# AJH_100m_ADSR_1_01.net
KiCad netlist of a schematic drawn in EAGLE
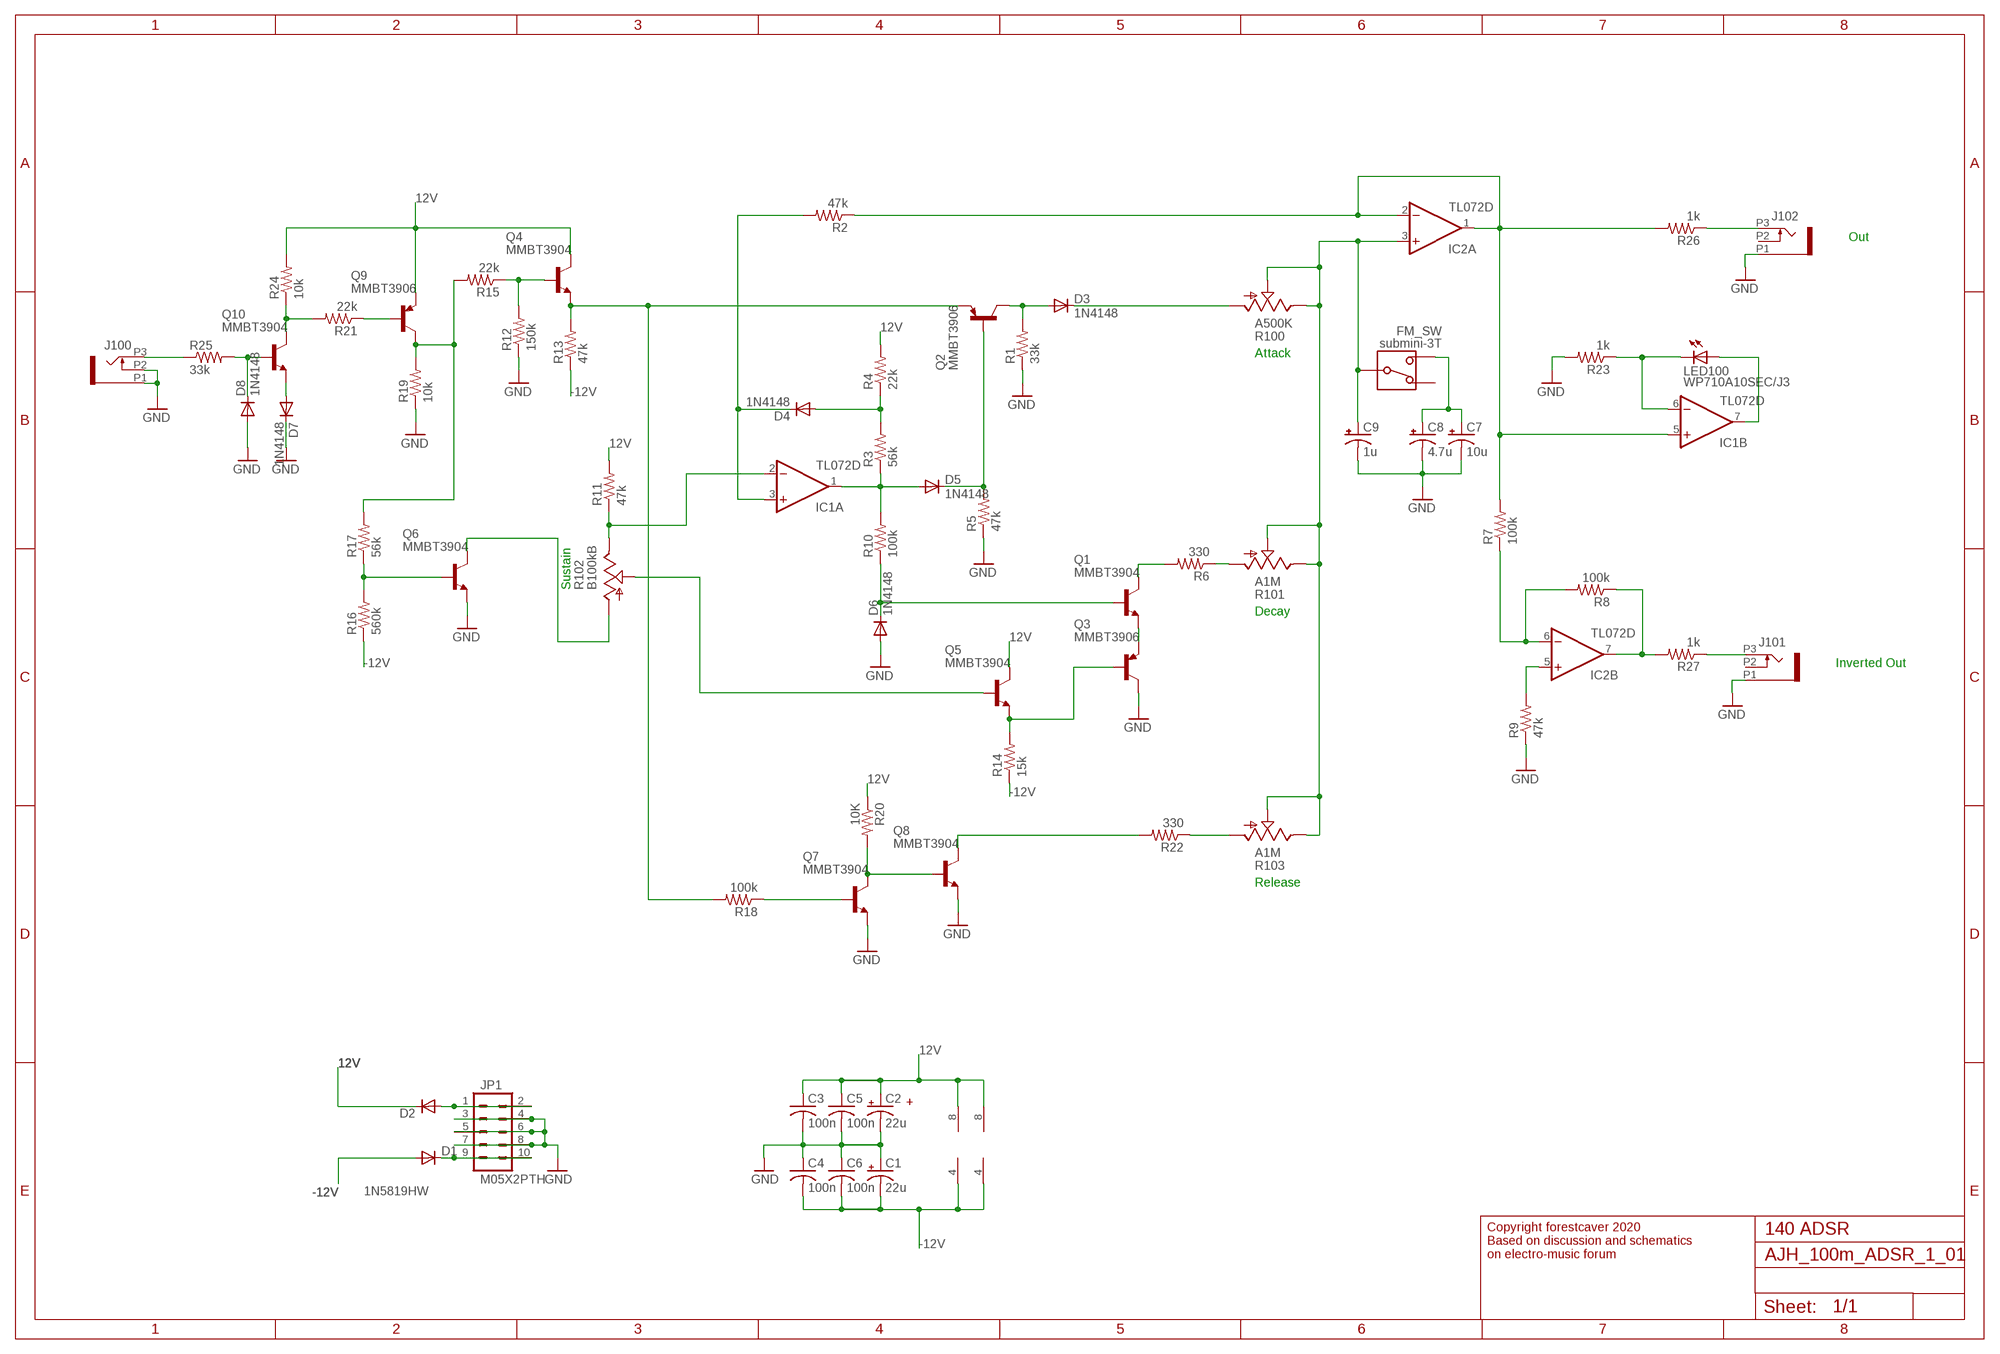
[diagram p0: schematic, sheet 1]

(export (version "E")
  (design (tool "Eeschema 10.0.6"))
  (components
    (comp (ref "C1")
      (value "22u")
      (footprint "eagle-import:PANASONIC_B")
      (libsource (lib "eagle-import") (part "CPOL-USB"))
    )
    (comp (ref "C2")
      (value "22u")
      (footprint "eagle-import:PANASONIC_B")
      (libsource (lib "eagle-import") (part "CPOL-USB"))
    )
    (comp (ref "C3")
      (value "100n")
      (footprint "eagle-import:C0603")
      (libsource (lib "eagle-import") (part "C-USC0603"))
    )
    (comp (ref "C4")
      (value "100n")
      (footprint "eagle-import:C0603")
      (libsource (lib "eagle-import") (part "C-USC0603"))
    )
    (comp (ref "C5")
      (value "100n")
      (footprint "eagle-import:C0603")
      (libsource (lib "eagle-import") (part "C-USC0603"))
    )
    (comp (ref "C6")
      (value "100n")
      (footprint "eagle-import:C0603")
      (libsource (lib "eagle-import") (part "C-USC0603"))
    )
    (comp (ref "C7")
      (value "10u")
      (footprint "eagle-import:PANASONIC_B")
      (libsource (lib "eagle-import") (part "CPOL-USB"))
    )
    (comp (ref "C8")
      (value "4.7u")
      (footprint "eagle-import:PANASONIC_B")
      (libsource (lib "eagle-import") (part "CPOL-USB"))
    )
    (comp (ref "C9")
      (value "1u")
      (footprint "eagle-import:PANASONIC_B")
      (libsource (lib "eagle-import") (part "CPOL-USB"))
    )
    (comp (ref "D1")
      (value "1N5819HW")
      (footprint "eagle-import:SOD123")
      (libsource (lib "eagle-import") (part "DIODE-SOD123"))
    )
    (comp (ref "D2")
      (value "1N5819HW")
      (footprint "eagle-import:SOD123")
      (libsource (lib "eagle-import") (part "DIODE-SOD123"))
    )
    (comp (ref "D3")
      (value "1N4148")
      (footprint "eagle-import:SOD323-W")
      (libsource (lib "eagle-import") (part "DIODE-SOD323-W"))
    )
    (comp (ref "D4")
      (value "1N4148")
      (footprint "eagle-import:SOD323-W")
      (libsource (lib "eagle-import") (part "DIODE-SOD323-W"))
    )
    (comp (ref "D5")
      (value "1N4148")
      (footprint "eagle-import:SOD323-W")
      (libsource (lib "eagle-import") (part "DIODE-SOD323-W"))
    )
    (comp (ref "D6")
      (value "1N4148")
      (footprint "eagle-import:SOD323-W")
      (libsource (lib "eagle-import") (part "DIODE-SOD323-W"))
    )
    (comp (ref "D7")
      (value "1N4148")
      (footprint "eagle-import:SOD323-W")
      (libsource (lib "eagle-import") (part "DIODE-SOD323-W"))
    )
    (comp (ref "D8")
      (value "1N4148")
      (footprint "eagle-import:SOD323-W")
      (libsource (lib "eagle-import") (part "DIODE-SOD323-W"))
    )
    (comp (ref "FM_SW")
      (value "submini-3T")
      (footprint "eagle-import:SPDT-SUB")
      (libsource (lib "eagle-import") (part "SPDTT"))
    )
    (comp (ref "IC1")
      (value "TL072D")
      (footprint "eagle-import:SO08")
      (libsource (lib "eagle-import") (part "TL072D"))
    )
    (comp (ref "IC2")
      (value "TL072D")
      (footprint "eagle-import:SO08")
      (libsource (lib "eagle-import") (part "TL072D"))
    )
    (comp (ref "J100")
      (value "PJ301_THONKICONN6")
      (footprint "eagle-import:WQP_PJ_301M6")
      (libsource (lib "eagle-import") (part "PJ301_THONKICONN6"))
    )
    (comp (ref "J101")
      (value "PJ301_THONKICONN6")
      (footprint "eagle-import:WQP_PJ_301M6")
      (libsource (lib "eagle-import") (part "PJ301_THONKICONN6"))
    )
    (comp (ref "J102")
      (value "PJ301_THONKICONN6")
      (footprint "eagle-import:WQP_PJ_301M6")
      (libsource (lib "eagle-import") (part "PJ301_THONKICONN6"))
    )
    (comp (ref "JP1")
      (value "M05X2PTH")
      (footprint "eagle-import:AVR_ICSP")
      (libsource (lib "eagle-import") (part "M05X2PTH"))
    )
    (comp (ref "LED100")
      (value "WP710A10SEC/J3")
      (footprint "eagle-import:LED3MM")
      (libsource (lib "eagle-import") (part "LED3MM"))
    )
    (comp (ref "Q1")
      (value "MMBT3904")
      (footprint "eagle-import:SOT23-BEC")
      (libsource (lib "eagle-import") (part "-NPN-SOT23-BECMMBT3904LT1"))
    )
    (comp (ref "Q2")
      (value "MMBT3906")
      (footprint "eagle-import:SOT23-BEC")
      (libsource (lib "eagle-import") (part "-PNP-SOT23-BECMMBT3906LT1"))
    )
    (comp (ref "Q3")
      (value "MMBT3906")
      (footprint "eagle-import:SOT23-BEC")
      (libsource (lib "eagle-import") (part "-PNP-SOT23-BECMMBT3906LT1"))
    )
    (comp (ref "Q4")
      (value "MMBT3904")
      (footprint "eagle-import:SOT23-BEC")
      (libsource (lib "eagle-import") (part "-NPN-SOT23-BECMMBT3904LT1"))
    )
    (comp (ref "Q5")
      (value "MMBT3904")
      (footprint "eagle-import:SOT23-BEC")
      (libsource (lib "eagle-import") (part "-NPN-SOT23-BECMMBT3904LT1"))
    )
    (comp (ref "Q6")
      (value "MMBT3904")
      (footprint "eagle-import:SOT23-BEC")
      (libsource (lib "eagle-import") (part "-NPN-SOT23-BECMMBT3904LT1"))
    )
    (comp (ref "Q7")
      (value "MMBT3904")
      (footprint "eagle-import:SOT23-BEC")
      (libsource (lib "eagle-import") (part "-NPN-SOT23-BECMMBT3904LT1"))
    )
    (comp (ref "Q8")
      (value "MMBT3904")
      (footprint "eagle-import:SOT23-BEC")
      (libsource (lib "eagle-import") (part "-NPN-SOT23-BECMMBT3904LT1"))
    )
    (comp (ref "Q9")
      (value "MMBT3906")
      (footprint "eagle-import:SOT23-BEC")
      (libsource (lib "eagle-import") (part "-PNP-SOT23-BECMMBT3906LT1"))
    )
    (comp (ref "Q10")
      (value "MMBT3904")
      (footprint "eagle-import:SOT23-BEC")
      (libsource (lib "eagle-import") (part "-NPN-SOT23-BECMMBT3904LT1"))
    )
    (comp (ref "R1")
      (value "33k")
      (footprint "eagle-import:R0603")
      (libsource (lib "eagle-import") (part "resistor_R-US_R0603"))
    )
    (comp (ref "R2")
      (value "47k")
      (footprint "eagle-import:R0603")
      (libsource (lib "eagle-import") (part "resistor_R-US_R0603"))
    )
    (comp (ref "R3")
      (value "56k")
      (footprint "eagle-import:R0603")
      (libsource (lib "eagle-import") (part "resistor_R-US_R0603"))
    )
    (comp (ref "R4")
      (value "22k")
      (footprint "eagle-import:R0603")
      (libsource (lib "eagle-import") (part "resistor_R-US_R0603"))
    )
    (comp (ref "R5")
      (value "47k")
      (footprint "eagle-import:R0603")
      (libsource (lib "eagle-import") (part "resistor_R-US_R0603"))
    )
    (comp (ref "R6")
      (value "330")
      (footprint "eagle-import:R0603")
      (libsource (lib "eagle-import") (part "resistor_R-US_R0603"))
    )
    (comp (ref "R7")
      (value "100k")
      (footprint "eagle-import:R0603")
      (libsource (lib "eagle-import") (part "resistor_R-US_R0603"))
    )
    (comp (ref "R8")
      (value "100k")
      (footprint "eagle-import:R0603")
      (libsource (lib "eagle-import") (part "resistor_R-US_R0603"))
    )
    (comp (ref "R9")
      (value "47k")
      (footprint "eagle-import:R0603")
      (libsource (lib "eagle-import") (part "resistor_R-US_R0603"))
    )
    (comp (ref "R10")
      (value "100k")
      (footprint "eagle-import:R0603")
      (libsource (lib "eagle-import") (part "resistor_R-US_R0603"))
    )
    (comp (ref "R11")
      (value "47k")
      (footprint "eagle-import:R0603")
      (libsource (lib "eagle-import") (part "resistor_R-US_R0603"))
    )
    (comp (ref "R12")
      (value "150k")
      (footprint "eagle-import:R0603")
      (libsource (lib "eagle-import") (part "resistor_R-US_R0603"))
    )
    (comp (ref "R13")
      (value "47k")
      (footprint "eagle-import:R0603")
      (libsource (lib "eagle-import") (part "resistor_R-US_R0603"))
    )
    (comp (ref "R14")
      (value "15k")
      (footprint "eagle-import:R0603")
      (libsource (lib "eagle-import") (part "resistor_R-US_R0603"))
    )
    (comp (ref "R15")
      (value "22k")
      (footprint "eagle-import:R0603")
      (libsource (lib "eagle-import") (part "resistor_R-US_R0603"))
    )
    (comp (ref "R16")
      (value "560k")
      (footprint "eagle-import:R0603")
      (libsource (lib "eagle-import") (part "resistor_R-US_R0603"))
    )
    (comp (ref "R17")
      (value "56k")
      (footprint "eagle-import:R0603")
      (libsource (lib "eagle-import") (part "resistor_R-US_R0603"))
    )
    (comp (ref "R18")
      (value "100k")
      (footprint "eagle-import:R0603")
      (libsource (lib "eagle-import") (part "resistor_R-US_R0603"))
    )
    (comp (ref "R19")
      (value "10k")
      (footprint "eagle-import:R0603")
      (libsource (lib "eagle-import") (part "resistor_R-US_R0603"))
    )
    (comp (ref "R20")
      (value "10K")
      (footprint "eagle-import:R0603")
      (libsource (lib "eagle-import") (part "resistor_R-US_R0603"))
    )
    (comp (ref "R21")
      (value "22k")
      (footprint "eagle-import:R0603")
      (libsource (lib "eagle-import") (part "resistor_R-US_R0603"))
    )
    (comp (ref "R22")
      (value "330")
      (footprint "eagle-import:R0603")
      (libsource (lib "eagle-import") (part "resistor_R-US_R0603"))
    )
    (comp (ref "R23")
      (value "1k")
      (footprint "eagle-import:R0603")
      (libsource (lib "eagle-import") (part "R-US_R0603"))
    )
    (comp (ref "R24")
      (value "10k")
      (footprint "eagle-import:R0603")
      (libsource (lib "eagle-import") (part "resistor_R-US_R0603"))
    )
    (comp (ref "R25")
      (value "33k")
      (footprint "eagle-import:R0603")
      (libsource (lib "eagle-import") (part "resistor_R-US_R0603"))
    )
    (comp (ref "R26")
      (value "1k")
      (footprint "eagle-import:R0603")
      (libsource (lib "eagle-import") (part "resistor_R-US_R0603"))
    )
    (comp (ref "R27")
      (value "1k")
      (footprint "eagle-import:R0603")
      (libsource (lib "eagle-import") (part "resistor_R-US_R0603"))
    )
    (comp (ref "R100")
      (value "A500K")
      (footprint "eagle-import:ALPS_POT_VERTICAL")
      (libsource (lib "eagle-import") (part "POT_USVERTICAL"))
    )
    (comp (ref "R101")
      (value "A1M")
      (footprint "eagle-import:ALPS_POT_VERTICAL")
      (libsource (lib "eagle-import") (part "POT_USVERTICAL"))
    )
    (comp (ref "R102")
      (value "B100kB")
      (footprint "eagle-import:ALPS_POT_VERTICAL")
      (libsource (lib "eagle-import") (part "POT_USVERTICAL"))
    )
    (comp (ref "R103")
      (value "A1M")
      (footprint "eagle-import:ALPS_POT_VERTICAL")
      (libsource (lib "eagle-import") (part "POT_USVERTICAL"))
    )
  )
  (nets
    (net (code "1") (name "/-12V") (class "Default")
      (node (ref "C1") (pin "-") (pinfunction "-_-") (pintype "passive"))
      (node (ref "C4") (pin "2") (pinfunction "2_2") (pintype "passive"))
      (node (ref "C6") (pin "2") (pinfunction "2_2") (pintype "passive"))
      (node (ref "D1") (pin "A") (pinfunction "A_A") (pintype "passive"))
      (node (ref "IC1") (pin "4") (pinfunction "V-_4") (pintype "power_in"))
      (node (ref "IC2") (pin "4") (pinfunction "V-_4") (pintype "power_in"))
      (node (ref "R13") (pin "1") (pinfunction "1_1") (pintype "passive"))
      (node (ref "R14") (pin "1") (pinfunction "1_1") (pintype "passive"))
      (node (ref "R16") (pin "1") (pinfunction "1_1") (pintype "passive"))
    )
    (net (code "2") (name "/12V") (class "Default")
      (node (ref "C2") (pin "+") (pinfunction "+_+") (pintype "passive"))
      (node (ref "C3") (pin "1") (pinfunction "1_1") (pintype "passive"))
      (node (ref "C5") (pin "1") (pinfunction "1_1") (pintype "passive"))
      (node (ref "D2") (pin "C") (pinfunction "C_C") (pintype "passive"))
      (node (ref "IC1") (pin "8") (pinfunction "V+_8") (pintype "power_in"))
      (node (ref "IC2") (pin "8") (pinfunction "V+_8") (pintype "power_in"))
      (node (ref "Q4") (pin "C") (pinfunction "C_C") (pintype "passive"))
      (node (ref "Q5") (pin "C") (pinfunction "C_C") (pintype "passive"))
      (node (ref "Q9") (pin "E") (pinfunction "E_E") (pintype "passive"))
      (node (ref "R11") (pin "2") (pinfunction "2_2") (pintype "passive"))
      (node (ref "R20") (pin "1") (pinfunction "1_1") (pintype "passive"))
      (node (ref "R24") (pin "2") (pinfunction "2_2") (pintype "passive"))
      (node (ref "R4") (pin "2") (pinfunction "2_2") (pintype "passive"))
    )
    (net (code "3") (name "GND") (class "Default")
      (node (ref "C1") (pin "+") (pinfunction "+_+") (pintype "passive"))
      (node (ref "C2") (pin "-") (pinfunction "-_-") (pintype "passive"))
      (node (ref "C3") (pin "2") (pinfunction "2_2") (pintype "passive"))
      (node (ref "C4") (pin "1") (pinfunction "1_1") (pintype "passive"))
      (node (ref "C5") (pin "2") (pinfunction "2_2") (pintype "passive"))
      (node (ref "C6") (pin "1") (pinfunction "1_1") (pintype "passive"))
      (node (ref "C7") (pin "-") (pinfunction "-_-") (pintype "passive"))
      (node (ref "C8") (pin "-") (pinfunction "-_-") (pintype "passive"))
      (node (ref "C9") (pin "-") (pinfunction "-_-") (pintype "passive"))
      (node (ref "D6") (pin "A") (pinfunction "A_A") (pintype "passive"))
      (node (ref "D7") (pin "C") (pinfunction "C_C") (pintype "passive"))
      (node (ref "D8") (pin "A") (pinfunction "A_A") (pintype "passive"))
      (node (ref "J100") (pin "P1") (pinfunction "1_P1") (pintype "passive"))
      (node (ref "J100") (pin "P2") (pinfunction "2_P2") (pintype "passive"))
      (node (ref "J101") (pin "P1") (pinfunction "1_P1") (pintype "passive"))
      (node (ref "J102") (pin "P1") (pinfunction "1_P1") (pintype "passive"))
      (node (ref "JP1") (pin "3") (pinfunction "3_3") (pintype "passive"))
      (node (ref "JP1") (pin "4") (pinfunction "4_4") (pintype "passive"))
      (node (ref "JP1") (pin "5") (pinfunction "5_5") (pintype "passive"))
      (node (ref "JP1") (pin "6") (pinfunction "6_6") (pintype "passive"))
      (node (ref "JP1") (pin "7") (pinfunction "7_7") (pintype "passive"))
      (node (ref "JP1") (pin "8") (pinfunction "8_8") (pintype "passive"))
      (node (ref "Q3") (pin "C") (pinfunction "C_C") (pintype "passive"))
      (node (ref "Q6") (pin "E") (pinfunction "E_E") (pintype "passive"))
      (node (ref "Q7") (pin "E") (pinfunction "E_E") (pintype "passive"))
      (node (ref "Q8") (pin "E") (pinfunction "E_E") (pintype "passive"))
      (node (ref "R1") (pin "1") (pinfunction "1_1") (pintype "passive"))
      (node (ref "R12") (pin "1") (pinfunction "1_1") (pintype "passive"))
      (node (ref "R19") (pin "1") (pinfunction "1_1") (pintype "passive"))
      (node (ref "R23") (pin "2") (pinfunction "2_2") (pintype "passive"))
      (node (ref "R5") (pin "1") (pinfunction "1_1") (pintype "passive"))
      (node (ref "R9") (pin "1") (pinfunction "1_1") (pintype "passive"))
    )
    (net (code "4") (name "Net-(C7-Pad+)") (class "Default")
      (node (ref "C7") (pin "+") (pinfunction "+_+") (pintype "passive"))
      (node (ref "C8") (pin "+") (pinfunction "+_+") (pintype "passive"))
      (node (ref "FM_SW") (pin "P$1") (pinfunction "P$1_P$1") (pintype "passive"))
    )
    (net (code "5") (name "Net-(D1-PadC)") (class "Default")
      (node (ref "D1") (pin "C") (pinfunction "C_C") (pintype "passive"))
      (node (ref "JP1") (pin "10") (pinfunction "10_10") (pintype "passive"))
      (node (ref "JP1") (pin "9") (pinfunction "9_9") (pintype "passive"))
    )
    (net (code "6") (name "Net-(D2-PadA)") (class "Default")
      (node (ref "D2") (pin "A") (pinfunction "A_A") (pintype "passive"))
      (node (ref "JP1") (pin "1") (pinfunction "1_1") (pintype "passive"))
      (node (ref "JP1") (pin "2") (pinfunction "2_2") (pintype "passive"))
    )
    (net (code "7") (name "Net-(D3-PadA)") (class "Default")
      (node (ref "D3") (pin "A") (pinfunction "A_A") (pintype "passive"))
      (node (ref "Q2") (pin "C") (pinfunction "C_C") (pintype "passive"))
      (node (ref "R1") (pin "2") (pinfunction "2_2") (pintype "passive"))
    )
    (net (code "8") (name "Net-(D4-PadA)") (class "Default")
      (node (ref "D4") (pin "A") (pinfunction "A_A") (pintype "passive"))
      (node (ref "R3") (pin "2") (pinfunction "2_2") (pintype "passive"))
      (node (ref "R4") (pin "1") (pinfunction "1_1") (pintype "passive"))
    )
    (net (code "9") (name "Net-(D5-PadC)") (class "Default")
      (node (ref "D5") (pin "C") (pinfunction "C_C") (pintype "passive"))
      (node (ref "Q2") (pin "B") (pinfunction "B_B") (pintype "passive"))
      (node (ref "R5") (pin "2") (pinfunction "2_2") (pintype "passive"))
    )
    (net (code "10") (name "Net-(D6-PadC)") (class "Default")
      (node (ref "D6") (pin "C") (pinfunction "C_C") (pintype "passive"))
      (node (ref "Q1") (pin "B") (pinfunction "B_B") (pintype "passive"))
      (node (ref "R10") (pin "1") (pinfunction "1_1") (pintype "passive"))
    )
    (net (code "11") (name "Net-(D7-PadA)") (class "Default")
      (node (ref "D7") (pin "A") (pinfunction "A_A") (pintype "passive"))
      (node (ref "Q10") (pin "E") (pinfunction "E_E") (pintype "passive"))
    )
    (net (code "12") (name "Net-(D8-PadC)") (class "Default")
      (node (ref "D8") (pin "C") (pinfunction "C_C") (pintype "passive"))
      (node (ref "Q10") (pin "B") (pinfunction "B_B") (pintype "passive"))
      (node (ref "R25") (pin "2") (pinfunction "2_2") (pintype "passive"))
    )
    (net (code "13") (name "Net-(IC1A-+IN)") (class "Default")
      (node (ref "D4") (pin "C") (pinfunction "C_C") (pintype "passive"))
      (node (ref "IC1") (pin "3") (pinfunction "+IN_3") (pintype "input"))
      (node (ref "R2") (pin "2") (pinfunction "2_2") (pintype "passive"))
    )
    (net (code "14") (name "Net-(IC1A--IN)") (class "Default")
      (node (ref "IC1") (pin "2") (pinfunction "-IN_2") (pintype "input"))
      (node (ref "R102") (pin "P$1") (pinfunction "E_P$1") (pintype "passive"))
      (node (ref "R11") (pin "1") (pinfunction "1_1") (pintype "passive"))
    )
    (net (code "15") (name "Net-(IC1A-OUT)") (class "Default")
      (node (ref "D5") (pin "A") (pinfunction "A_A") (pintype "passive"))
      (node (ref "IC1") (pin "1") (pinfunction "OUT_1") (pintype "output"))
      (node (ref "R10") (pin "2") (pinfunction "2_2") (pintype "passive"))
      (node (ref "R3") (pin "1") (pinfunction "1_1") (pintype "passive"))
    )
    (net (code "16") (name "Net-(IC1B-+IN)") (class "Default")
      (node (ref "IC1") (pin "5") (pinfunction "+IN_5") (pintype "input"))
      (node (ref "IC2") (pin "1") (pinfunction "OUT_1") (pintype "output"))
      (node (ref "IC2") (pin "2") (pinfunction "-IN_2") (pintype "input"))
      (node (ref "R2") (pin "1") (pinfunction "1_1") (pintype "passive"))
      (node (ref "R26") (pin "2") (pinfunction "2_2") (pintype "passive"))
      (node (ref "R7") (pin "2") (pinfunction "2_2") (pintype "passive"))
    )
    (net (code "17") (name "Net-(IC1B--IN)") (class "Default")
      (node (ref "IC1") (pin "6") (pinfunction "-IN_6") (pintype "input"))
      (node (ref "LED100") (pin "K") (pinfunction "C_K") (pintype "passive"))
      (node (ref "R23") (pin "1") (pinfunction "1_1") (pintype "passive"))
    )
    (net (code "18") (name "Net-(IC1B-OUT)") (class "Default")
      (node (ref "IC1") (pin "7") (pinfunction "OUT_7") (pintype "output"))
      (node (ref "LED100") (pin "A") (pinfunction "A_A") (pintype "passive"))
    )
    (net (code "19") (name "Net-(IC2A-+IN)") (class "Default")
      (node (ref "C9") (pin "+") (pinfunction "+_+") (pintype "passive"))
      (node (ref "FM_SW") (pin "P$2") (pinfunction "P$2_P$2") (pintype "passive"))
      (node (ref "IC2") (pin "3") (pinfunction "+IN_3") (pintype "input"))
      (node (ref "R100") (pin "P$1") (pinfunction "E_P$1") (pintype "passive"))
      (node (ref "R100") (pin "P$2") (pinfunction "S_P$2") (pintype "passive"))
      (node (ref "R101") (pin "P$1") (pinfunction "E_P$1") (pintype "passive"))
      (node (ref "R101") (pin "P$2") (pinfunction "S_P$2") (pintype "passive"))
      (node (ref "R103") (pin "P$1") (pinfunction "E_P$1") (pintype "passive"))
      (node (ref "R103") (pin "P$2") (pinfunction "S_P$2") (pintype "passive"))
    )
    (net (code "20") (name "Net-(IC2B-+IN)") (class "Default")
      (node (ref "IC2") (pin "5") (pinfunction "+IN_5") (pintype "input"))
      (node (ref "R9") (pin "2") (pinfunction "2_2") (pintype "passive"))
    )
    (net (code "21") (name "Net-(IC2B--IN)") (class "Default")
      (node (ref "IC2") (pin "6") (pinfunction "-IN_6") (pintype "input"))
      (node (ref "R7") (pin "1") (pinfunction "1_1") (pintype "passive"))
      (node (ref "R8") (pin "2") (pinfunction "2_2") (pintype "passive"))
    )
    (net (code "22") (name "Net-(IC2B-OUT)") (class "Default")
      (node (ref "IC2") (pin "7") (pinfunction "OUT_7") (pintype "output"))
      (node (ref "R27") (pin "2") (pinfunction "2_2") (pintype "passive"))
      (node (ref "R8") (pin "1") (pinfunction "1_1") (pintype "passive"))
    )
    (net (code "23") (name "Net-(J100-3)") (class "Default")
      (node (ref "J100") (pin "P3") (pinfunction "3_P3") (pintype "passive"))
      (node (ref "R25") (pin "1") (pinfunction "1_1") (pintype "passive"))
    )
    (net (code "24") (name "Net-(J101-3)") (class "Default")
      (node (ref "J101") (pin "P3") (pinfunction "3_P3") (pintype "passive"))
      (node (ref "R27") (pin "1") (pinfunction "1_1") (pintype "passive"))
    )
    (net (code "25") (name "Net-(J102-3)") (class "Default")
      (node (ref "J102") (pin "P3") (pinfunction "3_P3") (pintype "passive"))
      (node (ref "R26") (pin "1") (pinfunction "1_1") (pintype "passive"))
    )
    (net (code "26") (name "Net-(Q1-PadC)") (class "Default")
      (node (ref "Q1") (pin "C") (pinfunction "C_C") (pintype "passive"))
      (node (ref "R6") (pin "2") (pinfunction "2_2") (pintype "passive"))
    )
    (net (code "27") (name "Net-(Q1-PadE)") (class "Default")
      (node (ref "Q1") (pin "E") (pinfunction "E_E") (pintype "passive"))
      (node (ref "Q3") (pin "E") (pinfunction "E_E") (pintype "passive"))
    )
    (net (code "28") (name "Net-(Q2-PadE)") (class "Default")
      (node (ref "Q2") (pin "E") (pinfunction "E_E") (pintype "passive"))
      (node (ref "Q4") (pin "E") (pinfunction "E_E") (pintype "passive"))
      (node (ref "R13") (pin "2") (pinfunction "2_2") (pintype "passive"))
      (node (ref "R18") (pin "2") (pinfunction "2_2") (pintype "passive"))
    )
    (net (code "29") (name "Net-(Q3-PadB)") (class "Default")
      (node (ref "Q3") (pin "B") (pinfunction "B_B") (pintype "passive"))
      (node (ref "Q5") (pin "E") (pinfunction "E_E") (pintype "passive"))
      (node (ref "R14") (pin "2") (pinfunction "2_2") (pintype "passive"))
    )
    (net (code "30") (name "Net-(Q4-PadB)") (class "Default")
      (node (ref "Q4") (pin "B") (pinfunction "B_B") (pintype "passive"))
      (node (ref "R12") (pin "2") (pinfunction "2_2") (pintype "passive"))
      (node (ref "R15") (pin "1") (pinfunction "1_1") (pintype "passive"))
    )
    (net (code "31") (name "Net-(Q6-PadB)") (class "Default")
      (node (ref "Q6") (pin "B") (pinfunction "B_B") (pintype "passive"))
      (node (ref "R16") (pin "2") (pinfunction "2_2") (pintype "passive"))
      (node (ref "R17") (pin "1") (pinfunction "1_1") (pintype "passive"))
    )
    (net (code "32") (name "Net-(Q7-PadB)") (class "Default")
      (node (ref "Q7") (pin "B") (pinfunction "B_B") (pintype "passive"))
      (node (ref "R18") (pin "1") (pinfunction "1_1") (pintype "passive"))
    )
    (net (code "33") (name "Net-(Q7-PadC)") (class "Default")
      (node (ref "Q7") (pin "C") (pinfunction "C_C") (pintype "passive"))
      (node (ref "Q8") (pin "B") (pinfunction "B_B") (pintype "passive"))
      (node (ref "R20") (pin "2") (pinfunction "2_2") (pintype "passive"))
    )
    (net (code "34") (name "Net-(Q8-PadC)") (class "Default")
      (node (ref "Q8") (pin "C") (pinfunction "C_C") (pintype "passive"))
      (node (ref "R22") (pin "2") (pinfunction "2_2") (pintype "passive"))
    )
    (net (code "35") (name "Net-(Q9-PadB)") (class "Default")
      (node (ref "Q9") (pin "B") (pinfunction "B_B") (pintype "passive"))
      (node (ref "R21") (pin "1") (pinfunction "1_1") (pintype "passive"))
    )
    (net (code "36") (name "Net-(Q9-PadC)") (class "Default")
      (node (ref "Q9") (pin "C") (pinfunction "C_C") (pintype "passive"))
      (node (ref "R15") (pin "2") (pinfunction "2_2") (pintype "passive"))
      (node (ref "R17") (pin "2") (pinfunction "2_2") (pintype "passive"))
      (node (ref "R19") (pin "2") (pinfunction "2_2") (pintype "passive"))
    )
    (net (code "37") (name "Net-(Q10-PadC)") (class "Default")
      (node (ref "Q10") (pin "C") (pinfunction "C_C") (pintype "passive"))
      (node (ref "R21") (pin "2") (pinfunction "2_2") (pintype "passive"))
      (node (ref "R24") (pin "1") (pinfunction "1_1") (pintype "passive"))
    )
    (net (code "38") (name "Net-(R100-A)") (class "Default")
      (node (ref "D3") (pin "C") (pinfunction "C_C") (pintype "passive"))
      (node (ref "R100") (pin "P$3") (pinfunction "A_P$3") (pintype "passive"))
    )
    (net (code "39") (name "Net-(R101-A)") (class "Default")
      (node (ref "R101") (pin "P$3") (pinfunction "A_P$3") (pintype "passive"))
      (node (ref "R6") (pin "1") (pinfunction "1_1") (pintype "passive"))
    )
    (net (code "40") (name "Net-(R102-A)") (class "Default")
      (node (ref "Q6") (pin "C") (pinfunction "C_C") (pintype "passive"))
      (node (ref "R102") (pin "P$3") (pinfunction "A_P$3") (pintype "passive"))
    )
    (net (code "41") (name "Net-(R102-S)") (class "Default")
      (node (ref "Q5") (pin "B") (pinfunction "B_B") (pintype "passive"))
      (node (ref "R102") (pin "P$2") (pinfunction "S_P$2") (pintype "passive"))
    )
    (net (code "42") (name "Net-(R103-A)") (class "Default")
      (node (ref "R103") (pin "P$3") (pinfunction "A_P$3") (pintype "passive"))
      (node (ref "R22") (pin "1") (pinfunction "1_1") (pintype "passive"))
    )
    (net (code "43") (name "unconnected-(FM_SW-PadP$3)") (class "Default")
      (node (ref "FM_SW") (pin "P$3") (pinfunction "P$3_P$3") (pintype "passive"))
    )
    (net (code "44") (name "unconnected-(J101-2-PadP2)") (class "Default")
      (node (ref "J101") (pin "P2") (pinfunction "2_P2") (pintype "passive"))
    )
    (net (code "45") (name "unconnected-(J102-2-PadP2)") (class "Default")
      (node (ref "J102") (pin "P2") (pinfunction "2_P2") (pintype "passive"))
    )
  )
)
